# NusbioMCU.net
KiCad netlist of a schematic drawn in EAGLE
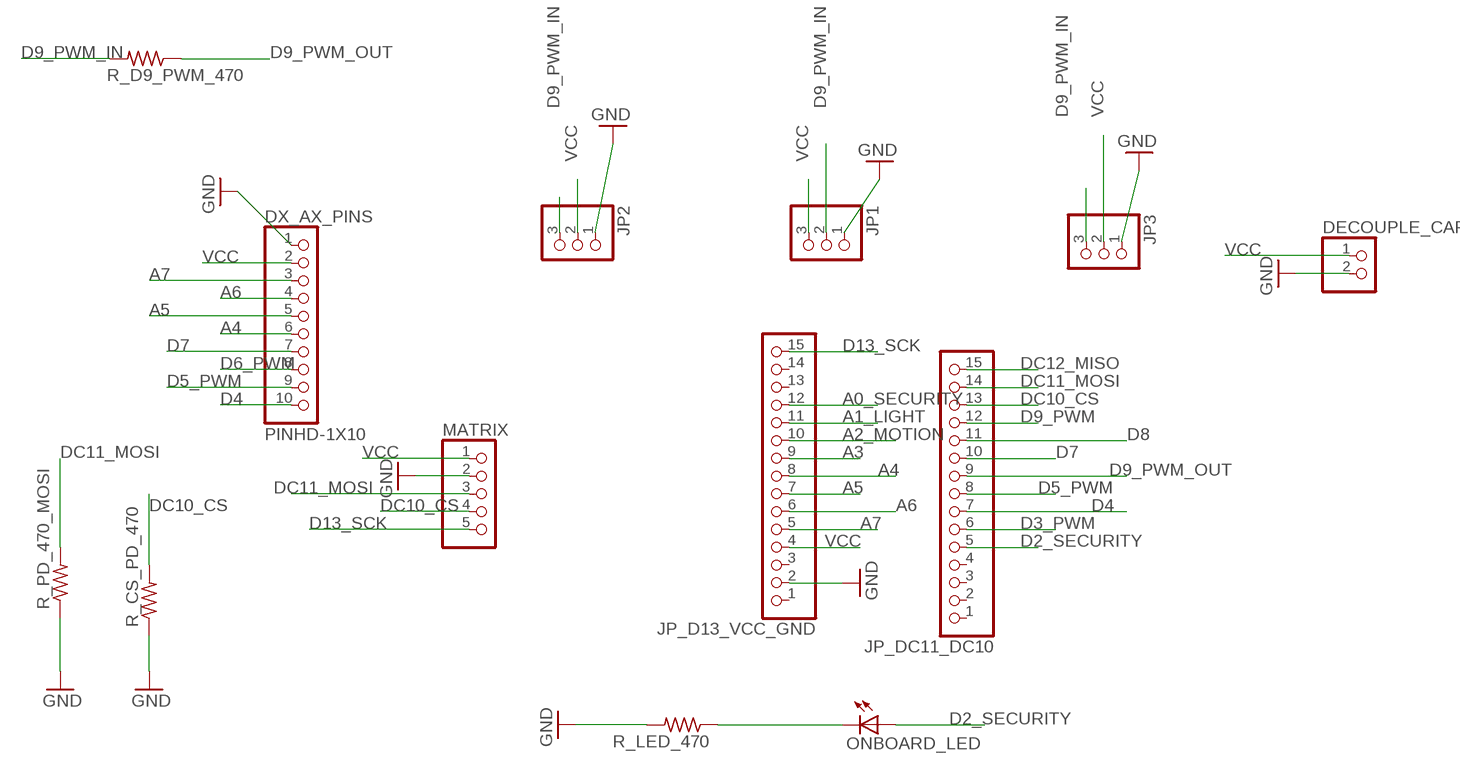
[diagram p0: schematic, sheet 1]

(export (version "E")
  (design (tool "Eeschema 10.0.6"))
  (components
    (comp (ref "DECOUPLE_CAP")
      (value "PINHD-1X2")
      (footprint "eagle-import:1X02")
      (libsource (lib "eagle-import") (part "PINHD-1X2"))
    )
    (comp (ref "DX_AX_PINS")
      (value "PINHD-1X10")
      (footprint "eagle-import:1X10-BIG")
      (libsource (lib "eagle-import") (part "PINHD-1X10"))
    )
    (comp (ref "JP1")
      (value "PINHD-1X3")
      (footprint "eagle-import:1X03")
      (libsource (lib "eagle-import") (part "PINHD-1X3"))
    )
    (comp (ref "JP2")
      (value "PINHD-1X3")
      (footprint "eagle-import:1X03")
      (libsource (lib "eagle-import") (part "PINHD-1X3"))
    )
    (comp (ref "JP3")
      (value "PINHD-1X3")
      (footprint "eagle-import:1X03")
      (libsource (lib "eagle-import") (part "PINHD-1X3"))
    )
    (comp (ref "JP_D13_VCC_GND")
      (value "PINHD-1X15")
      (footprint "eagle-import:1X15")
      (libsource (lib "eagle-import") (part "PINHD-1X15"))
    )
    (comp (ref "JP_DC11_DC10")
      (value "PINHD-1X15")
      (footprint "eagle-import:1X15")
      (libsource (lib "eagle-import") (part "PINHD-1X15"))
    )
    (comp (ref "MATRIX")
      (value "PINHD-1X5")
      (footprint "eagle-import:1X05")
      (libsource (lib "eagle-import") (part "PINHD-1X5"))
    )
    (comp (ref "ONBOARD_LED")
      (value "LEDSMT1206")
      (footprint "eagle-import:1206")
      (libsource (lib "eagle-import") (part "LEDSMT1206"))
    )
    (comp (ref "R_CS_PD_470")
      (value "R-US_R1206")
      (footprint "eagle-import:R1206")
      (libsource (lib "eagle-import") (part "R-US_R1206"))
    )
    (comp (ref "R_D9_PWM_470")
      (value "R-US_R1206")
      (footprint "eagle-import:R1206")
      (libsource (lib "eagle-import") (part "R-US_R1206"))
    )
    (comp (ref "R_LED_470")
      (value "R-US_R1206")
      (footprint "eagle-import:R1206")
      (libsource (lib "eagle-import") (part "R-US_R1206"))
    )
    (comp (ref "R_PD_470_MOSI")
      (value "R-US_R1206")
      (footprint "eagle-import:R1206")
      (libsource (lib "eagle-import") (part "R-US_R1206"))
    )
  )
  (nets
    (net (code "1") (name "/A0_SECURITY") (class "Default")
      (node (ref "JP_D13_VCC_GND") (pin "12") (pinfunction "12_12") (pintype "passive"))
    )
    (net (code "2") (name "/A1_LIGHT") (class "Default")
      (node (ref "JP_D13_VCC_GND") (pin "11") (pinfunction "11_11") (pintype "passive"))
    )
    (net (code "3") (name "/A2_MOTION") (class "Default")
      (node (ref "JP_D13_VCC_GND") (pin "10") (pinfunction "10_10") (pintype "passive"))
    )
    (net (code "4") (name "/A3") (class "Default")
      (node (ref "JP_D13_VCC_GND") (pin "9") (pinfunction "9_9") (pintype "passive"))
    )
    (net (code "5") (name "/A4") (class "Default")
      (node (ref "DX_AX_PINS") (pin "6") (pinfunction "6_6") (pintype "passive"))
      (node (ref "JP_D13_VCC_GND") (pin "8") (pinfunction "8_8") (pintype "passive"))
    )
    (net (code "6") (name "/A5") (class "Default")
      (node (ref "DX_AX_PINS") (pin "5") (pinfunction "5_5") (pintype "passive"))
      (node (ref "JP_D13_VCC_GND") (pin "7") (pinfunction "7_7") (pintype "passive"))
    )
    (net (code "7") (name "/A6") (class "Default")
      (node (ref "DX_AX_PINS") (pin "4") (pinfunction "4_4") (pintype "passive"))
      (node (ref "JP_D13_VCC_GND") (pin "6") (pinfunction "6_6") (pintype "passive"))
    )
    (net (code "8") (name "/A7") (class "Default")
      (node (ref "DX_AX_PINS") (pin "3") (pinfunction "3_3") (pintype "passive"))
      (node (ref "JP_D13_VCC_GND") (pin "5") (pinfunction "5_5") (pintype "passive"))
    )
    (net (code "9") (name "/D2_SECURITY") (class "Default")
      (node (ref "JP_DC11_DC10") (pin "5") (pinfunction "5_5") (pintype "passive"))
      (node (ref "ONBOARD_LED") (pin "A") (pinfunction "A_A") (pintype "passive"))
    )
    (net (code "10") (name "/D3_PWM") (class "Default")
      (node (ref "JP_DC11_DC10") (pin "6") (pinfunction "6_6") (pintype "passive"))
    )
    (net (code "11") (name "/D4") (class "Default")
      (node (ref "DX_AX_PINS") (pin "10") (pinfunction "10_10") (pintype "passive"))
      (node (ref "JP_DC11_DC10") (pin "7") (pinfunction "7_7") (pintype "passive"))
    )
    (net (code "12") (name "/D5_PWM") (class "Default")
      (node (ref "DX_AX_PINS") (pin "9") (pinfunction "9_9") (pintype "passive"))
      (node (ref "JP_DC11_DC10") (pin "8") (pinfunction "8_8") (pintype "passive"))
    )
    (net (code "13") (name "/D6_PWM") (class "Default")
      (node (ref "DX_AX_PINS") (pin "8") (pinfunction "8_8") (pintype "passive"))
    )
    (net (code "14") (name "/D7") (class "Default")
      (node (ref "DX_AX_PINS") (pin "7") (pinfunction "7_7") (pintype "passive"))
      (node (ref "JP_DC11_DC10") (pin "10") (pinfunction "10_10") (pintype "passive"))
    )
    (net (code "15") (name "/D8") (class "Default")
      (node (ref "JP_DC11_DC10") (pin "11") (pinfunction "11_11") (pintype "passive"))
    )
    (net (code "16") (name "/D9_PWM") (class "Default")
      (node (ref "JP_DC11_DC10") (pin "12") (pinfunction "12_12") (pintype "passive"))
    )
    (net (code "17") (name "/D9_PWM_IN") (class "Default")
      (node (ref "JP1") (pin "2") (pinfunction "2_2") (pintype "passive"))
      (node (ref "JP2") (pin "3") (pinfunction "3_3") (pintype "passive"))
      (node (ref "JP3") (pin "3") (pinfunction "3_3") (pintype "passive"))
      (node (ref "R_D9_PWM_470") (pin "2") (pinfunction "2_2") (pintype "passive"))
    )
    (net (code "18") (name "/D9_PWM_OUT") (class "Default")
      (node (ref "JP_DC11_DC10") (pin "9") (pinfunction "9_9") (pintype "passive"))
      (node (ref "R_D9_PWM_470") (pin "1") (pinfunction "1_1") (pintype "passive"))
    )
    (net (code "19") (name "/D13_SCK") (class "Default")
      (node (ref "JP_D13_VCC_GND") (pin "15") (pinfunction "15_15") (pintype "passive"))
      (node (ref "MATRIX") (pin "5") (pinfunction "5_5") (pintype "passive"))
    )
    (net (code "20") (name "/DC10_CS") (class "Default")
      (node (ref "JP_DC11_DC10") (pin "13") (pinfunction "13_13") (pintype "passive"))
      (node (ref "MATRIX") (pin "4") (pinfunction "4_4") (pintype "passive"))
      (node (ref "R_CS_PD_470") (pin "2") (pinfunction "2_2") (pintype "passive"))
    )
    (net (code "21") (name "/DC11_MOSI") (class "Default")
      (node (ref "JP_DC11_DC10") (pin "14") (pinfunction "14_14") (pintype "passive"))
      (node (ref "MATRIX") (pin "3") (pinfunction "3_3") (pintype "passive"))
      (node (ref "R_PD_470_MOSI") (pin "2") (pinfunction "2_2") (pintype "passive"))
    )
    (net (code "22") (name "/DC12_MISO") (class "Default")
      (node (ref "JP_DC11_DC10") (pin "15") (pinfunction "15_15") (pintype "passive"))
    )
    (net (code "23") (name "/VCC") (class "Default")
      (node (ref "DECOUPLE_CAP") (pin "1") (pinfunction "1_1") (pintype "passive"))
      (node (ref "DX_AX_PINS") (pin "2") (pinfunction "2_2") (pintype "passive"))
      (node (ref "JP1") (pin "3") (pinfunction "3_3") (pintype "passive"))
      (node (ref "JP2") (pin "2") (pinfunction "2_2") (pintype "passive"))
      (node (ref "JP3") (pin "2") (pinfunction "2_2") (pintype "passive"))
      (node (ref "JP_D13_VCC_GND") (pin "4") (pinfunction "4_4") (pintype "passive"))
      (node (ref "MATRIX") (pin "1") (pinfunction "1_1") (pintype "passive"))
    )
    (net (code "24") (name "GND") (class "Default")
      (node (ref "DECOUPLE_CAP") (pin "2") (pinfunction "2_2") (pintype "passive"))
      (node (ref "DX_AX_PINS") (pin "1") (pinfunction "1_1") (pintype "passive"))
      (node (ref "JP1") (pin "1") (pinfunction "1_1") (pintype "passive"))
      (node (ref "JP2") (pin "1") (pinfunction "1_1") (pintype "passive"))
      (node (ref "JP3") (pin "1") (pinfunction "1_1") (pintype "passive"))
      (node (ref "JP_D13_VCC_GND") (pin "2") (pinfunction "2_2") (pintype "passive"))
      (node (ref "MATRIX") (pin "2") (pinfunction "2_2") (pintype "passive"))
      (node (ref "R_CS_PD_470") (pin "1") (pinfunction "1_1") (pintype "passive"))
      (node (ref "R_LED_470") (pin "2") (pinfunction "2_2") (pintype "passive"))
      (node (ref "R_PD_470_MOSI") (pin "1") (pinfunction "1_1") (pintype "passive"))
    )
    (net (code "25") (name "Net-(ONBOARD_LED-PadC)") (class "Default")
      (node (ref "ONBOARD_LED") (pin "C") (pinfunction "C_C") (pintype "passive"))
      (node (ref "R_LED_470") (pin "1") (pinfunction "1_1") (pintype "passive"))
    )
    (net (code "26") (name "unconnected-(JP_D13_VCC_GND-Pad1)") (class "Default")
      (node (ref "JP_D13_VCC_GND") (pin "1") (pinfunction "1_1") (pintype "passive"))
    )
    (net (code "27") (name "unconnected-(JP_D13_VCC_GND-Pad3)") (class "Default")
      (node (ref "JP_D13_VCC_GND") (pin "3") (pinfunction "3_3") (pintype "passive"))
    )
    (net (code "28") (name "unconnected-(JP_D13_VCC_GND-Pad13)") (class "Default")
      (node (ref "JP_D13_VCC_GND") (pin "13") (pinfunction "13_13") (pintype "passive"))
    )
    (net (code "29") (name "unconnected-(JP_D13_VCC_GND-Pad14)") (class "Default")
      (node (ref "JP_D13_VCC_GND") (pin "14") (pinfunction "14_14") (pintype "passive"))
    )
    (net (code "30") (name "unconnected-(JP_DC11_DC10-Pad1)") (class "Default")
      (node (ref "JP_DC11_DC10") (pin "1") (pinfunction "1_1") (pintype "passive"))
    )
    (net (code "31") (name "unconnected-(JP_DC11_DC10-Pad2)") (class "Default")
      (node (ref "JP_DC11_DC10") (pin "2") (pinfunction "2_2") (pintype "passive"))
    )
    (net (code "32") (name "unconnected-(JP_DC11_DC10-Pad3)") (class "Default")
      (node (ref "JP_DC11_DC10") (pin "3") (pinfunction "3_3") (pintype "passive"))
    )
    (net (code "33") (name "unconnected-(JP_DC11_DC10-Pad4)") (class "Default")
      (node (ref "JP_DC11_DC10") (pin "4") (pinfunction "4_4") (pintype "passive"))
    )
  )
)
